# full_adder.net
KiCad netlist of a schematic drawn in EAGLE
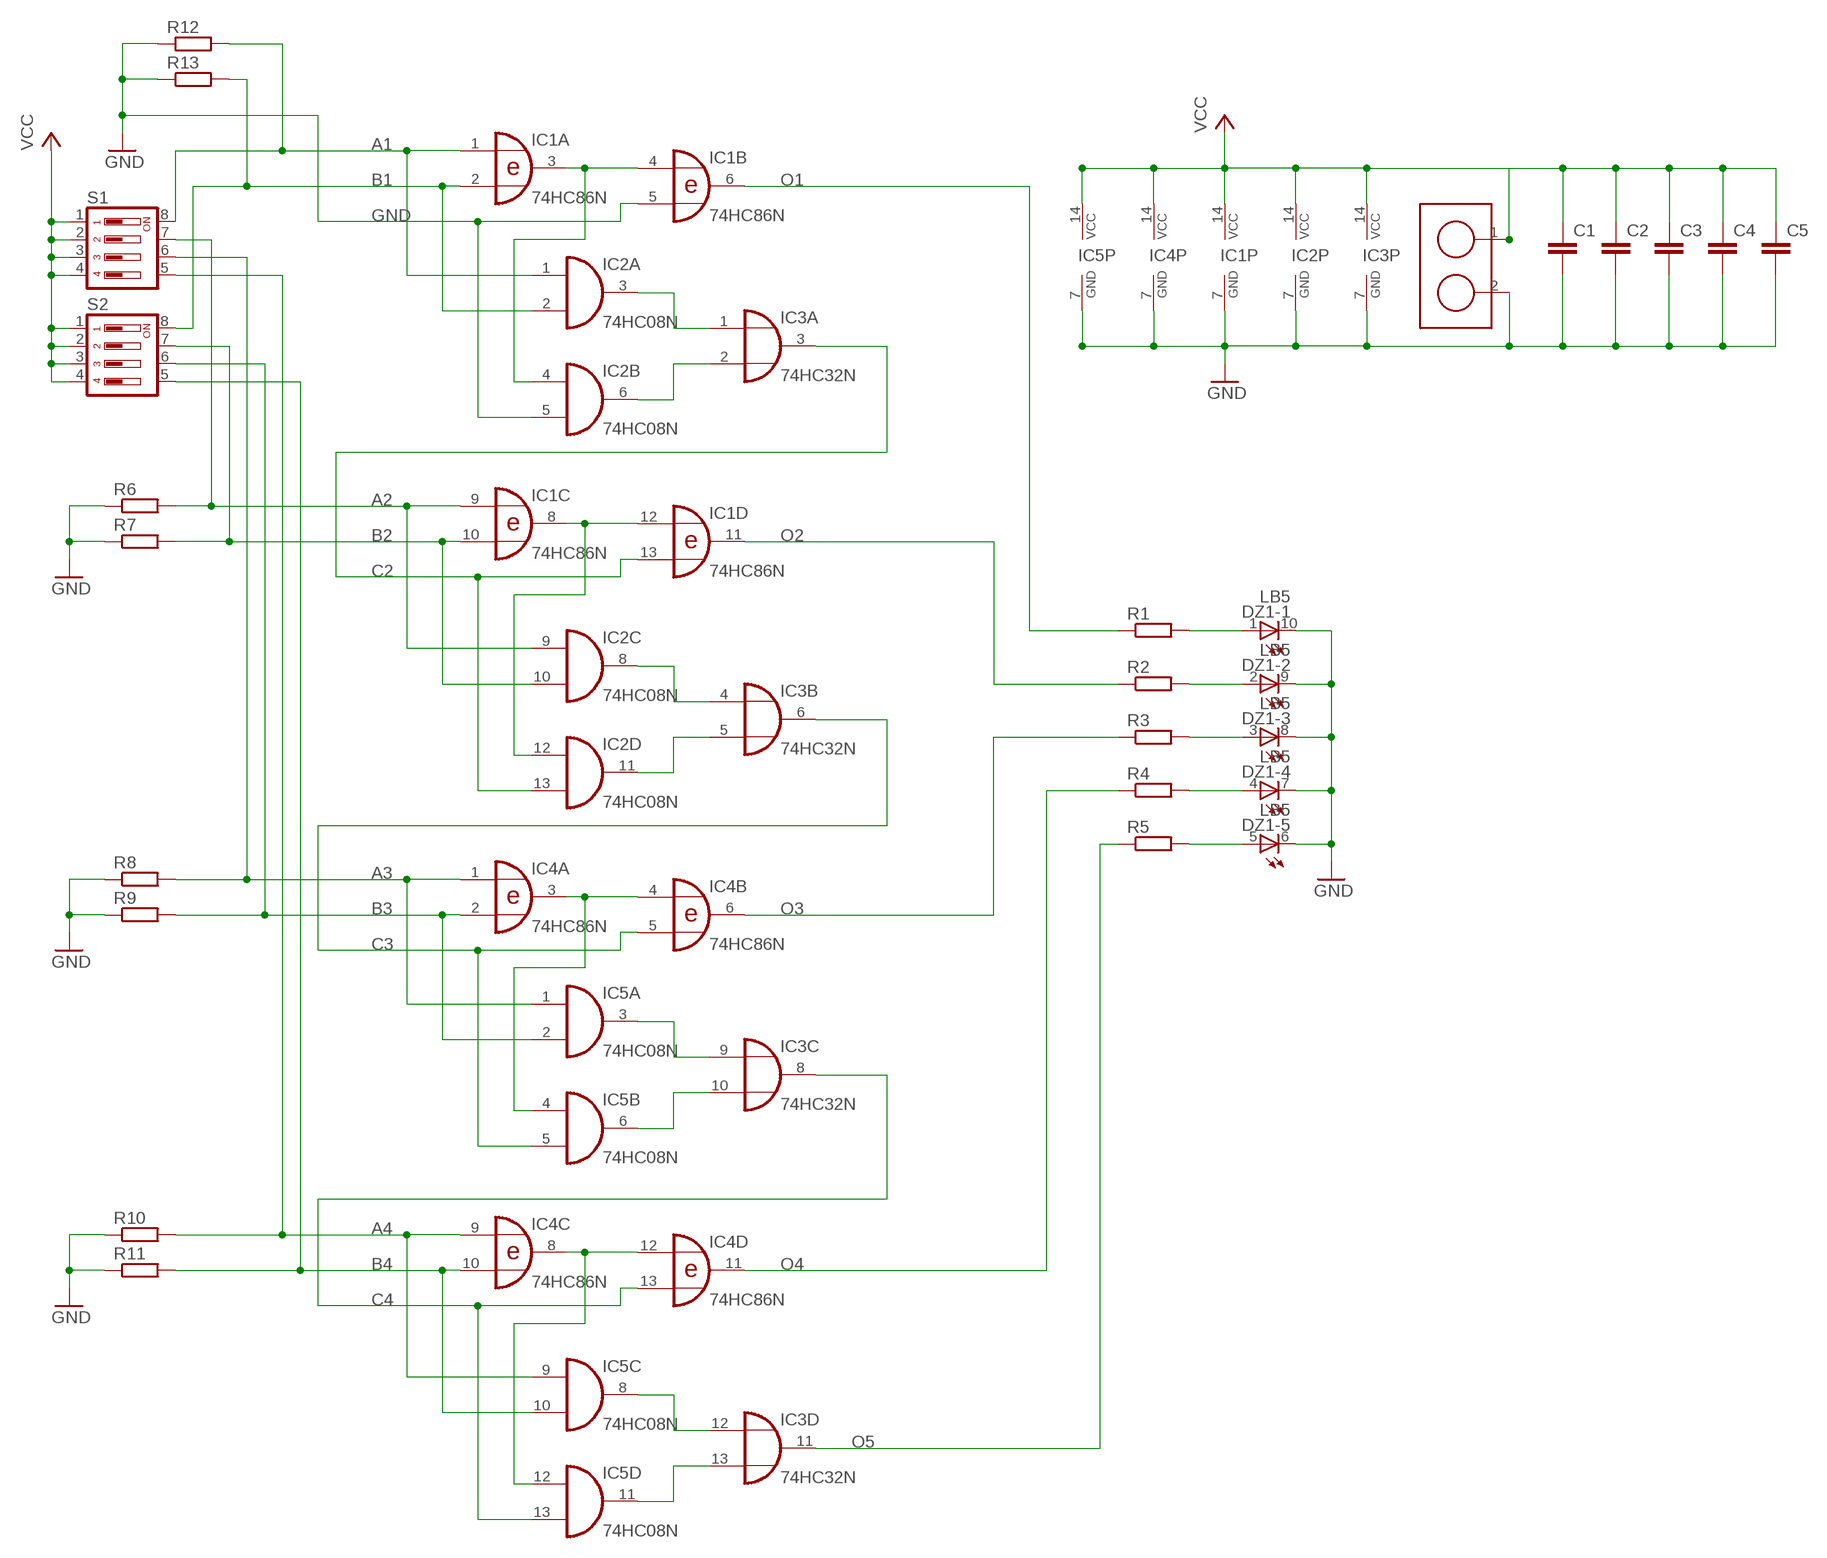
[diagram p0: schematic, sheet 1]

(export (version "E")
  (design (tool "Eeschema 10.0.6"))
  (components
    (comp (ref "C1")
      (value "C-EU025-025X050")
      (footprint "eagle-import:C025-025X050")
      (libsource (lib "eagle-import") (part "C-EU025-025X050"))
    )
    (comp (ref "C2")
      (value "C-EU025-025X050")
      (footprint "eagle-import:C025-025X050")
      (libsource (lib "eagle-import") (part "C-EU025-025X050"))
    )
    (comp (ref "C3")
      (value "C-EU025-025X050")
      (footprint "eagle-import:C025-025X050")
      (libsource (lib "eagle-import") (part "C-EU025-025X050"))
    )
    (comp (ref "C4")
      (value "C-EU025-025X050")
      (footprint "eagle-import:C025-025X050")
      (libsource (lib "eagle-import") (part "C-EU025-025X050"))
    )
    (comp (ref "C5")
      (value "C-EU025-025X050")
      (footprint "eagle-import:C025-025X050")
      (libsource (lib "eagle-import") (part "C-EU025-025X050"))
    )
    (comp (ref "DZ1")
      (value "LB5")
      (footprint "eagle-import:LB5")
      (libsource (lib "eagle-import") (part "LB5"))
    )
    (comp (ref "IC1")
      (value "74HC86N")
      (footprint "eagle-import:DIL14")
      (libsource (lib "eagle-import") (part "7486NHC"))
    )
    (comp (ref "IC2")
      (value "74HC08N")
      (footprint "eagle-import:DIL14")
      (libsource (lib "eagle-import") (part "7408NHC"))
    )
    (comp (ref "IC3")
      (value "74HC32N")
      (footprint "eagle-import:DIL14")
      (libsource (lib "eagle-import") (part "7432NHC"))
    )
    (comp (ref "IC4")
      (value "74HC86N")
      (footprint "eagle-import:DIL14")
      (libsource (lib "eagle-import") (part "7486NHC"))
    )
    (comp (ref "IC5")
      (value "74HC08N")
      (footprint "eagle-import:DIL14")
      (libsource (lib "eagle-import") (part "7408NHC"))
    )
    (comp (ref "R1")
      (value "R-EU_0204/7")
      (footprint "eagle-import:0204_7")
      (libsource (lib "eagle-import") (part "R-EU_0204/7"))
    )
    (comp (ref "R2")
      (value "R-EU_0204/7")
      (footprint "eagle-import:0204_7")
      (libsource (lib "eagle-import") (part "R-EU_0204/7"))
    )
    (comp (ref "R3")
      (value "R-EU_0204/7")
      (footprint "eagle-import:0204_7")
      (libsource (lib "eagle-import") (part "R-EU_0204/7"))
    )
    (comp (ref "R4")
      (value "R-EU_0204/7")
      (footprint "eagle-import:0204_7")
      (libsource (lib "eagle-import") (part "R-EU_0204/7"))
    )
    (comp (ref "R5")
      (value "R-EU_0204/7")
      (footprint "eagle-import:0204_7")
      (libsource (lib "eagle-import") (part "R-EU_0204/7"))
    )
    (comp (ref "R6")
      (value "10K")
      (footprint "eagle-import:0204_7")
      (libsource (lib "eagle-import") (part "R-EU_0204/7"))
    )
    (comp (ref "R7")
      (value "10K")
      (footprint "eagle-import:0204_7")
      (libsource (lib "eagle-import") (part "R-EU_0204/7"))
    )
    (comp (ref "R8")
      (value "10K")
      (footprint "eagle-import:0204_7")
      (libsource (lib "eagle-import") (part "R-EU_0204/7"))
    )
    (comp (ref "R9")
      (value "10K")
      (footprint "eagle-import:0204_7")
      (libsource (lib "eagle-import") (part "R-EU_0204/7"))
    )
    (comp (ref "R10")
      (value "10K")
      (footprint "eagle-import:0204_7")
      (libsource (lib "eagle-import") (part "R-EU_0204/7"))
    )
    (comp (ref "R11")
      (value "10K")
      (footprint "eagle-import:0204_7")
      (libsource (lib "eagle-import") (part "R-EU_0204/7"))
    )
    (comp (ref "R12")
      (value "10K")
      (footprint "eagle-import:0204_7")
      (libsource (lib "eagle-import") (part "R-EU_0204/7"))
    )
    (comp (ref "R13")
      (value "10K")
      (footprint "eagle-import:0204_7")
      (libsource (lib "eagle-import") (part "R-EU_0204/7"))
    )
    (comp (ref "S1")
      (value "DS04")
      (footprint "eagle-import:DS-04")
      (libsource (lib "eagle-import") (part "DS04"))
    )
    (comp (ref "S2")
      (value "DS04")
      (footprint "eagle-import:DS-04")
      (libsource (lib "eagle-import") (part "DS04"))
    )
    (comp (ref "U$5")
      (value "TB2")
      (footprint "eagle-import:TB2")
      (libsource (lib "eagle-import") (part "TB2"))
    )
  )
  (nets
    (net (code "1") (name "/A1") (class "Default")
      (node (ref "IC1") (pin "1") (pinfunction "I0_1") (pintype "input"))
      (node (ref "IC2") (pin "1") (pinfunction "I0_1") (pintype "input"))
      (node (ref "R12") (pin "2") (pinfunction "2_2") (pintype "passive"))
      (node (ref "S1") (pin "8") (pinfunction "8_8") (pintype "passive"))
    )
    (net (code "2") (name "/A2") (class "Default")
      (node (ref "IC1") (pin "9") (pinfunction "I0_9") (pintype "input"))
      (node (ref "IC2") (pin "9") (pinfunction "I0_9") (pintype "input"))
      (node (ref "R6") (pin "2") (pinfunction "2_2") (pintype "passive"))
      (node (ref "S1") (pin "7") (pinfunction "7_7") (pintype "passive"))
    )
    (net (code "3") (name "/A3") (class "Default")
      (node (ref "IC4") (pin "1") (pinfunction "I0_1") (pintype "input"))
      (node (ref "IC5") (pin "1") (pinfunction "I0_1") (pintype "input"))
      (node (ref "R8") (pin "2") (pinfunction "2_2") (pintype "passive"))
      (node (ref "S1") (pin "6") (pinfunction "6_6") (pintype "passive"))
    )
    (net (code "4") (name "/A4") (class "Default")
      (node (ref "IC4") (pin "9") (pinfunction "I0_9") (pintype "input"))
      (node (ref "IC5") (pin "9") (pinfunction "I0_9") (pintype "input"))
      (node (ref "R10") (pin "2") (pinfunction "2_2") (pintype "passive"))
      (node (ref "S1") (pin "5") (pinfunction "5_5") (pintype "passive"))
    )
    (net (code "5") (name "/B1") (class "Default")
      (node (ref "IC1") (pin "2") (pinfunction "I1_2") (pintype "input"))
      (node (ref "IC2") (pin "2") (pinfunction "I1_2") (pintype "input"))
      (node (ref "R13") (pin "2") (pinfunction "2_2") (pintype "passive"))
      (node (ref "S2") (pin "8") (pinfunction "8_8") (pintype "passive"))
    )
    (net (code "6") (name "/B2") (class "Default")
      (node (ref "IC1") (pin "10") (pinfunction "I1_10") (pintype "input"))
      (node (ref "IC2") (pin "10") (pinfunction "I1_10") (pintype "input"))
      (node (ref "R7") (pin "2") (pinfunction "2_2") (pintype "passive"))
      (node (ref "S2") (pin "7") (pinfunction "7_7") (pintype "passive"))
    )
    (net (code "7") (name "/B3") (class "Default")
      (node (ref "IC4") (pin "2") (pinfunction "I1_2") (pintype "input"))
      (node (ref "IC5") (pin "2") (pinfunction "I1_2") (pintype "input"))
      (node (ref "R9") (pin "2") (pinfunction "2_2") (pintype "passive"))
      (node (ref "S2") (pin "6") (pinfunction "6_6") (pintype "passive"))
    )
    (net (code "8") (name "/B4") (class "Default")
      (node (ref "IC4") (pin "10") (pinfunction "I1_10") (pintype "input"))
      (node (ref "IC5") (pin "10") (pinfunction "I1_10") (pintype "input"))
      (node (ref "R11") (pin "2") (pinfunction "2_2") (pintype "passive"))
      (node (ref "S2") (pin "5") (pinfunction "5_5") (pintype "passive"))
    )
    (net (code "9") (name "/C2") (class "Default")
      (node (ref "IC1") (pin "13") (pinfunction "I1_13") (pintype "input"))
      (node (ref "IC2") (pin "13") (pinfunction "I1_13") (pintype "input"))
      (node (ref "IC3") (pin "3") (pinfunction "O_3") (pintype "output"))
    )
    (net (code "10") (name "/C3") (class "Default")
      (node (ref "IC3") (pin "6") (pinfunction "O_6") (pintype "output"))
      (node (ref "IC4") (pin "5") (pinfunction "I1_5") (pintype "input"))
      (node (ref "IC5") (pin "5") (pinfunction "I1_5") (pintype "input"))
    )
    (net (code "11") (name "/C4") (class "Default")
      (node (ref "IC3") (pin "8") (pinfunction "O_8") (pintype "output"))
      (node (ref "IC4") (pin "13") (pinfunction "I1_13") (pintype "input"))
      (node (ref "IC5") (pin "13") (pinfunction "I1_13") (pintype "input"))
    )
    (net (code "12") (name "/O1") (class "Default")
      (node (ref "IC1") (pin "6") (pinfunction "O_6") (pintype "output"))
      (node (ref "R1") (pin "1") (pinfunction "1_1") (pintype "passive"))
    )
    (net (code "13") (name "/O2") (class "Default")
      (node (ref "IC1") (pin "11") (pinfunction "O_11") (pintype "output"))
      (node (ref "R2") (pin "1") (pinfunction "1_1") (pintype "passive"))
    )
    (net (code "14") (name "/O3") (class "Default")
      (node (ref "IC4") (pin "6") (pinfunction "O_6") (pintype "output"))
      (node (ref "R3") (pin "1") (pinfunction "1_1") (pintype "passive"))
    )
    (net (code "15") (name "/O4") (class "Default")
      (node (ref "IC4") (pin "11") (pinfunction "O_11") (pintype "output"))
      (node (ref "R4") (pin "1") (pinfunction "1_1") (pintype "passive"))
    )
    (net (code "16") (name "/O5") (class "Default")
      (node (ref "IC3") (pin "11") (pinfunction "O_11") (pintype "output"))
      (node (ref "R5") (pin "1") (pinfunction "1_1") (pintype "passive"))
    )
    (net (code "17") (name "GND") (class "Default")
      (node (ref "C1") (pin "2") (pinfunction "2_2") (pintype "passive"))
      (node (ref "C2") (pin "2") (pinfunction "2_2") (pintype "passive"))
      (node (ref "C3") (pin "2") (pinfunction "2_2") (pintype "passive"))
      (node (ref "C4") (pin "2") (pinfunction "2_2") (pintype "passive"))
      (node (ref "C5") (pin "2") (pinfunction "2_2") (pintype "passive"))
      (node (ref "DZ1") (pin "10") (pinfunction "C_10") (pintype "passive"))
      (node (ref "DZ1") (pin "6") (pinfunction "C_6") (pintype "passive"))
      (node (ref "DZ1") (pin "7") (pinfunction "C_7") (pintype "passive"))
      (node (ref "DZ1") (pin "8") (pinfunction "C_8") (pintype "passive"))
      (node (ref "DZ1") (pin "9") (pinfunction "C_9") (pintype "passive"))
      (node (ref "IC1") (pin "5") (pinfunction "I1_5") (pintype "input"))
      (node (ref "IC1") (pin "7") (pinfunction "GND_7") (pintype "power_in"))
      (node (ref "IC2") (pin "5") (pinfunction "I1_5") (pintype "input"))
      (node (ref "IC2") (pin "7") (pinfunction "GND_7") (pintype "power_in"))
      (node (ref "IC3") (pin "7") (pinfunction "GND_7") (pintype "power_in"))
      (node (ref "IC4") (pin "7") (pinfunction "GND_7") (pintype "power_in"))
      (node (ref "IC5") (pin "7") (pinfunction "GND_7") (pintype "power_in"))
      (node (ref "R10") (pin "1") (pinfunction "1_1") (pintype "passive"))
      (node (ref "R11") (pin "1") (pinfunction "1_1") (pintype "passive"))
      (node (ref "R12") (pin "1") (pinfunction "1_1") (pintype "passive"))
      (node (ref "R13") (pin "1") (pinfunction "1_1") (pintype "passive"))
      (node (ref "R6") (pin "1") (pinfunction "1_1") (pintype "passive"))
      (node (ref "R7") (pin "1") (pinfunction "1_1") (pintype "passive"))
      (node (ref "R8") (pin "1") (pinfunction "1_1") (pintype "passive"))
      (node (ref "R9") (pin "1") (pinfunction "1_1") (pintype "passive"))
      (node (ref "U$5") (pin "2") (pinfunction "P$2_2") (pintype "bidirectional"))
    )
    (net (code "18") (name "Net-(DZ1A-A)") (class "Default")
      (node (ref "DZ1") (pin "1") (pinfunction "A_1") (pintype "passive"))
      (node (ref "R1") (pin "2") (pinfunction "2_2") (pintype "passive"))
    )
    (net (code "19") (name "Net-(DZ1B-A)") (class "Default")
      (node (ref "DZ1") (pin "2") (pinfunction "A_2") (pintype "passive"))
      (node (ref "R2") (pin "2") (pinfunction "2_2") (pintype "passive"))
    )
    (net (code "20") (name "Net-(DZ1C-A)") (class "Default")
      (node (ref "DZ1") (pin "3") (pinfunction "A_3") (pintype "passive"))
      (node (ref "R3") (pin "2") (pinfunction "2_2") (pintype "passive"))
    )
    (net (code "21") (name "Net-(DZ1D-A)") (class "Default")
      (node (ref "DZ1") (pin "4") (pinfunction "A_4") (pintype "passive"))
      (node (ref "R4") (pin "2") (pinfunction "2_2") (pintype "passive"))
    )
    (net (code "22") (name "Net-(DZ1E-A)") (class "Default")
      (node (ref "DZ1") (pin "5") (pinfunction "A_5") (pintype "passive"))
      (node (ref "R5") (pin "2") (pinfunction "2_2") (pintype "passive"))
    )
    (net (code "23") (name "Net-(IC1A-O)") (class "Default")
      (node (ref "IC1") (pin "3") (pinfunction "O_3") (pintype "output"))
      (node (ref "IC1") (pin "4") (pinfunction "I0_4") (pintype "input"))
      (node (ref "IC2") (pin "4") (pinfunction "I0_4") (pintype "input"))
    )
    (net (code "24") (name "Net-(IC1C-O)") (class "Default")
      (node (ref "IC1") (pin "12") (pinfunction "I0_12") (pintype "input"))
      (node (ref "IC1") (pin "8") (pinfunction "O_8") (pintype "output"))
      (node (ref "IC2") (pin "12") (pinfunction "I0_12") (pintype "input"))
    )
    (net (code "25") (name "Net-(IC2A-O)") (class "Default")
      (node (ref "IC2") (pin "3") (pinfunction "O_3") (pintype "output"))
      (node (ref "IC3") (pin "1") (pinfunction "I0_1") (pintype "input"))
    )
    (net (code "26") (name "Net-(IC2B-O)") (class "Default")
      (node (ref "IC2") (pin "6") (pinfunction "O_6") (pintype "output"))
      (node (ref "IC3") (pin "2") (pinfunction "I1_2") (pintype "input"))
    )
    (net (code "27") (name "Net-(IC2C-O)") (class "Default")
      (node (ref "IC2") (pin "8") (pinfunction "O_8") (pintype "output"))
      (node (ref "IC3") (pin "4") (pinfunction "I0_4") (pintype "input"))
    )
    (net (code "28") (name "Net-(IC2D-O)") (class "Default")
      (node (ref "IC2") (pin "11") (pinfunction "O_11") (pintype "output"))
      (node (ref "IC3") (pin "5") (pinfunction "I1_5") (pintype "input"))
    )
    (net (code "29") (name "Net-(IC3C-I0)") (class "Default")
      (node (ref "IC3") (pin "9") (pinfunction "I0_9") (pintype "input"))
      (node (ref "IC5") (pin "3") (pinfunction "O_3") (pintype "output"))
    )
    (net (code "30") (name "Net-(IC3C-I1)") (class "Default")
      (node (ref "IC3") (pin "10") (pinfunction "I1_10") (pintype "input"))
      (node (ref "IC5") (pin "6") (pinfunction "O_6") (pintype "output"))
    )
    (net (code "31") (name "Net-(IC3D-I0)") (class "Default")
      (node (ref "IC3") (pin "12") (pinfunction "I0_12") (pintype "input"))
      (node (ref "IC5") (pin "8") (pinfunction "O_8") (pintype "output"))
    )
    (net (code "32") (name "Net-(IC3D-I1)") (class "Default")
      (node (ref "IC3") (pin "13") (pinfunction "I1_13") (pintype "input"))
      (node (ref "IC5") (pin "11") (pinfunction "O_11") (pintype "output"))
    )
    (net (code "33") (name "Net-(IC4A-O)") (class "Default")
      (node (ref "IC4") (pin "3") (pinfunction "O_3") (pintype "output"))
      (node (ref "IC4") (pin "4") (pinfunction "I0_4") (pintype "input"))
      (node (ref "IC5") (pin "4") (pinfunction "I0_4") (pintype "input"))
    )
    (net (code "34") (name "Net-(IC4C-O)") (class "Default")
      (node (ref "IC4") (pin "12") (pinfunction "I0_12") (pintype "input"))
      (node (ref "IC4") (pin "8") (pinfunction "O_8") (pintype "output"))
      (node (ref "IC5") (pin "12") (pinfunction "I0_12") (pintype "input"))
    )
    (net (code "35") (name "VCC") (class "Default")
      (node (ref "C1") (pin "1") (pinfunction "1_1") (pintype "passive"))
      (node (ref "C2") (pin "1") (pinfunction "1_1") (pintype "passive"))
      (node (ref "C3") (pin "1") (pinfunction "1_1") (pintype "passive"))
      (node (ref "C4") (pin "1") (pinfunction "1_1") (pintype "passive"))
      (node (ref "C5") (pin "1") (pinfunction "1_1") (pintype "passive"))
      (node (ref "IC1") (pin "14") (pinfunction "VCC_14") (pintype "power_in"))
      (node (ref "IC2") (pin "14") (pinfunction "VCC_14") (pintype "power_in"))
      (node (ref "IC3") (pin "14") (pinfunction "VCC_14") (pintype "power_in"))
      (node (ref "IC4") (pin "14") (pinfunction "VCC_14") (pintype "power_in"))
      (node (ref "IC5") (pin "14") (pinfunction "VCC_14") (pintype "power_in"))
      (node (ref "S1") (pin "1") (pinfunction "1_1") (pintype "passive"))
      (node (ref "S1") (pin "2") (pinfunction "2_2") (pintype "passive"))
      (node (ref "S1") (pin "3") (pinfunction "3_3") (pintype "passive"))
      (node (ref "S1") (pin "4") (pinfunction "4_4") (pintype "passive"))
      (node (ref "S2") (pin "1") (pinfunction "1_1") (pintype "passive"))
      (node (ref "S2") (pin "2") (pinfunction "2_2") (pintype "passive"))
      (node (ref "S2") (pin "3") (pinfunction "3_3") (pintype "passive"))
      (node (ref "S2") (pin "4") (pinfunction "4_4") (pintype "passive"))
      (node (ref "U$5") (pin "1") (pinfunction "P$1_1") (pintype "bidirectional"))
    )
  )
)
